# Sonar-Three-Amp-Block.net
KiCad netlist of a schematic drawn in EAGLE
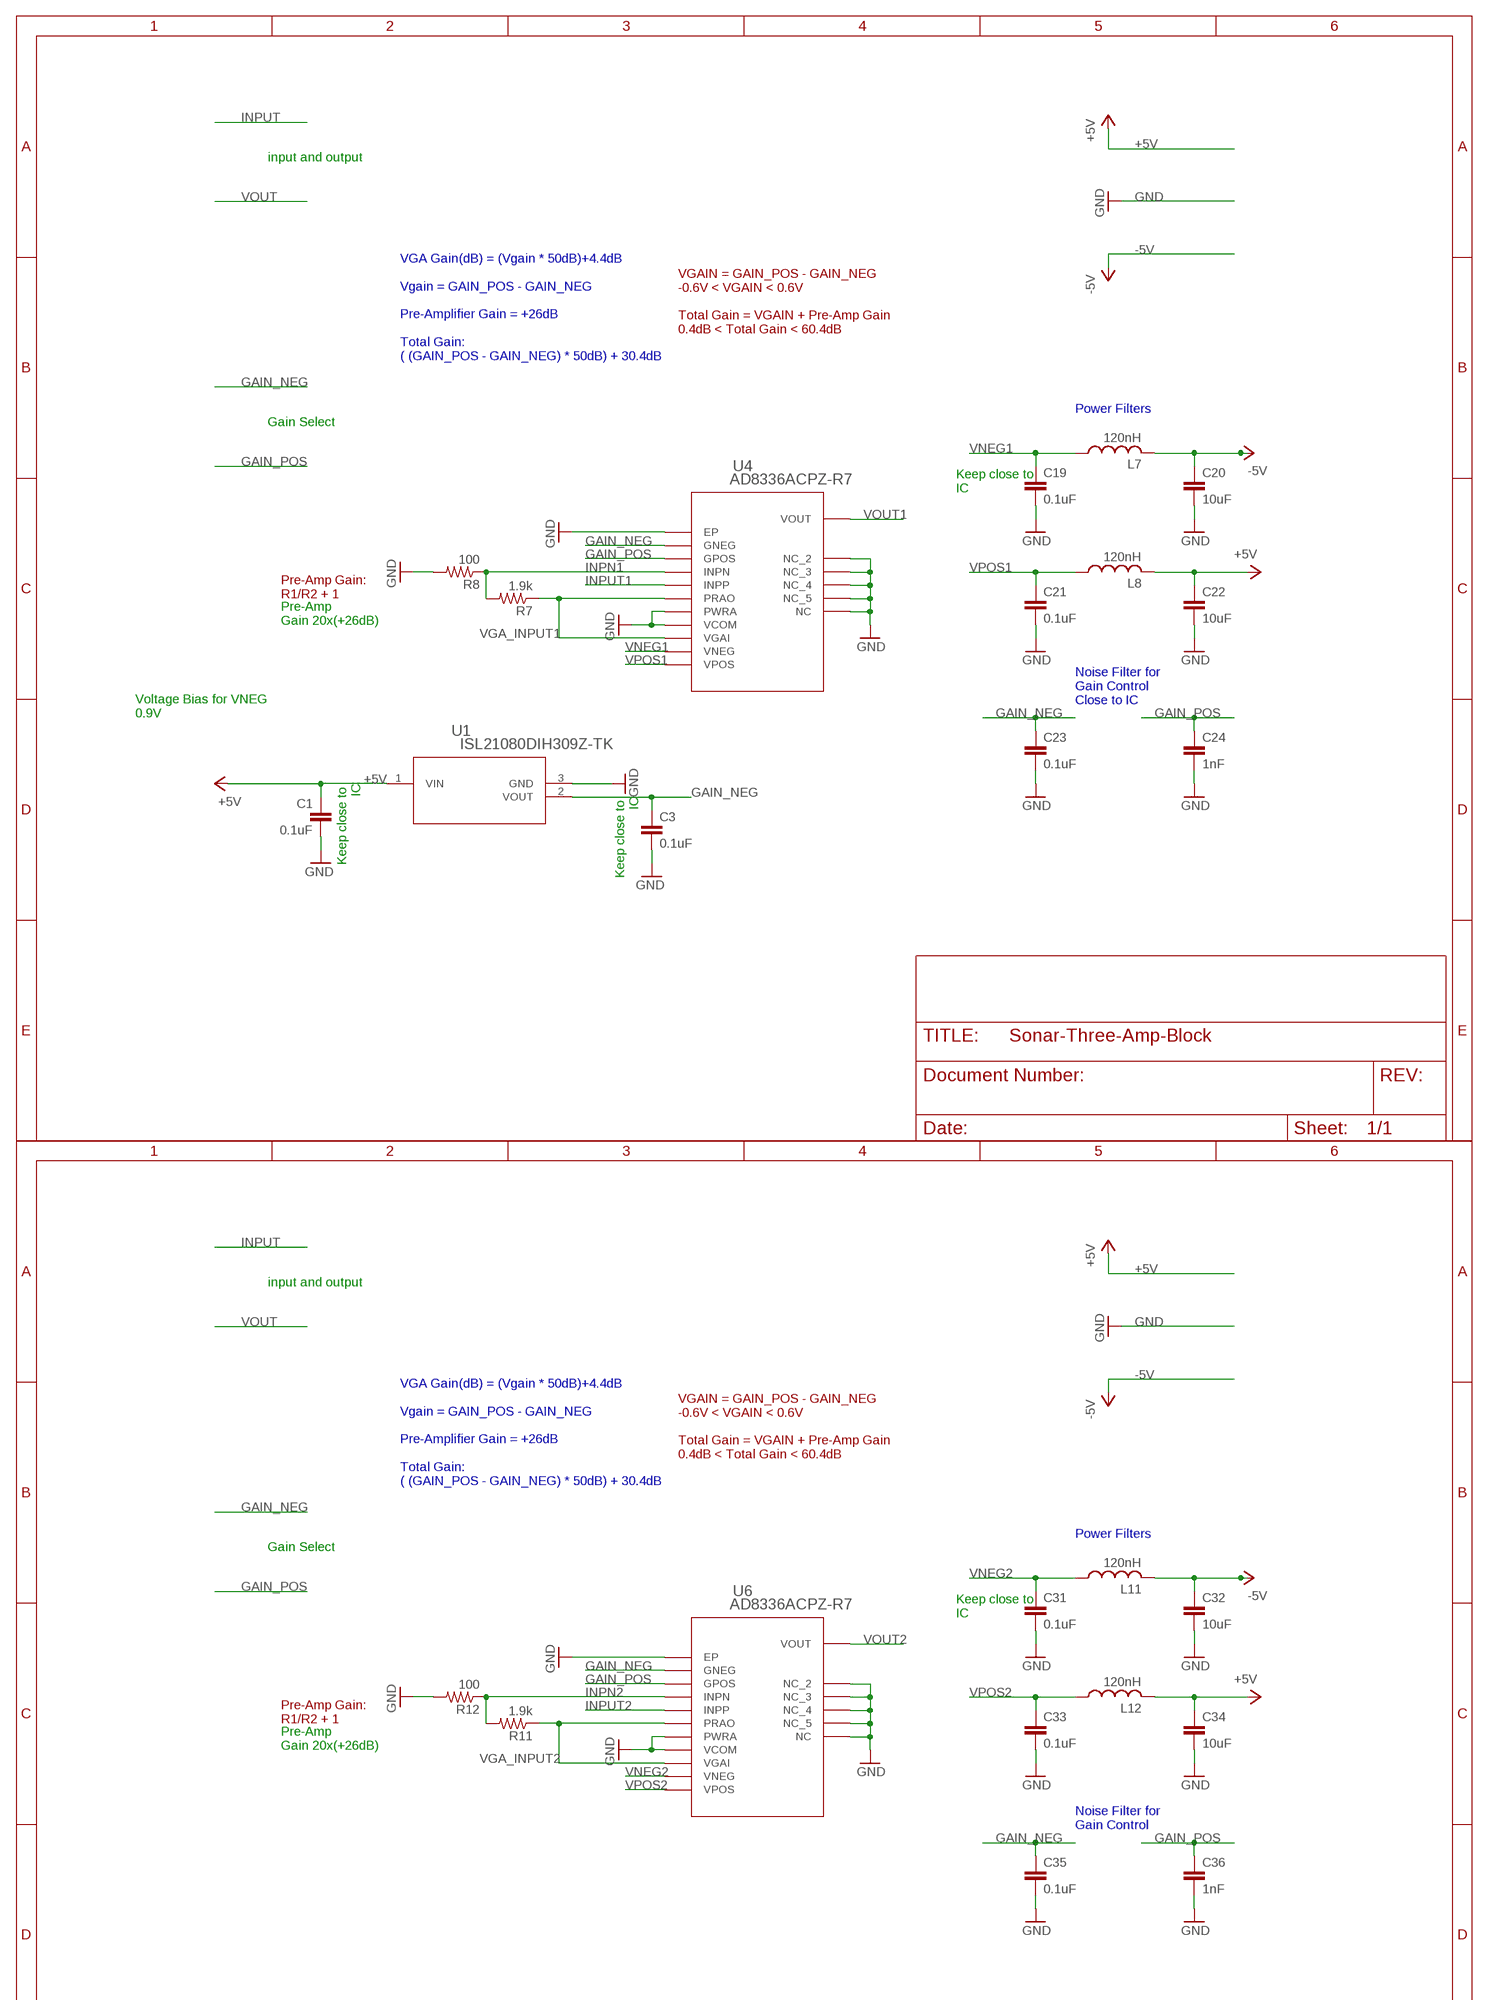
[diagram p0: schematic, sheet 1, part 1 of 2]
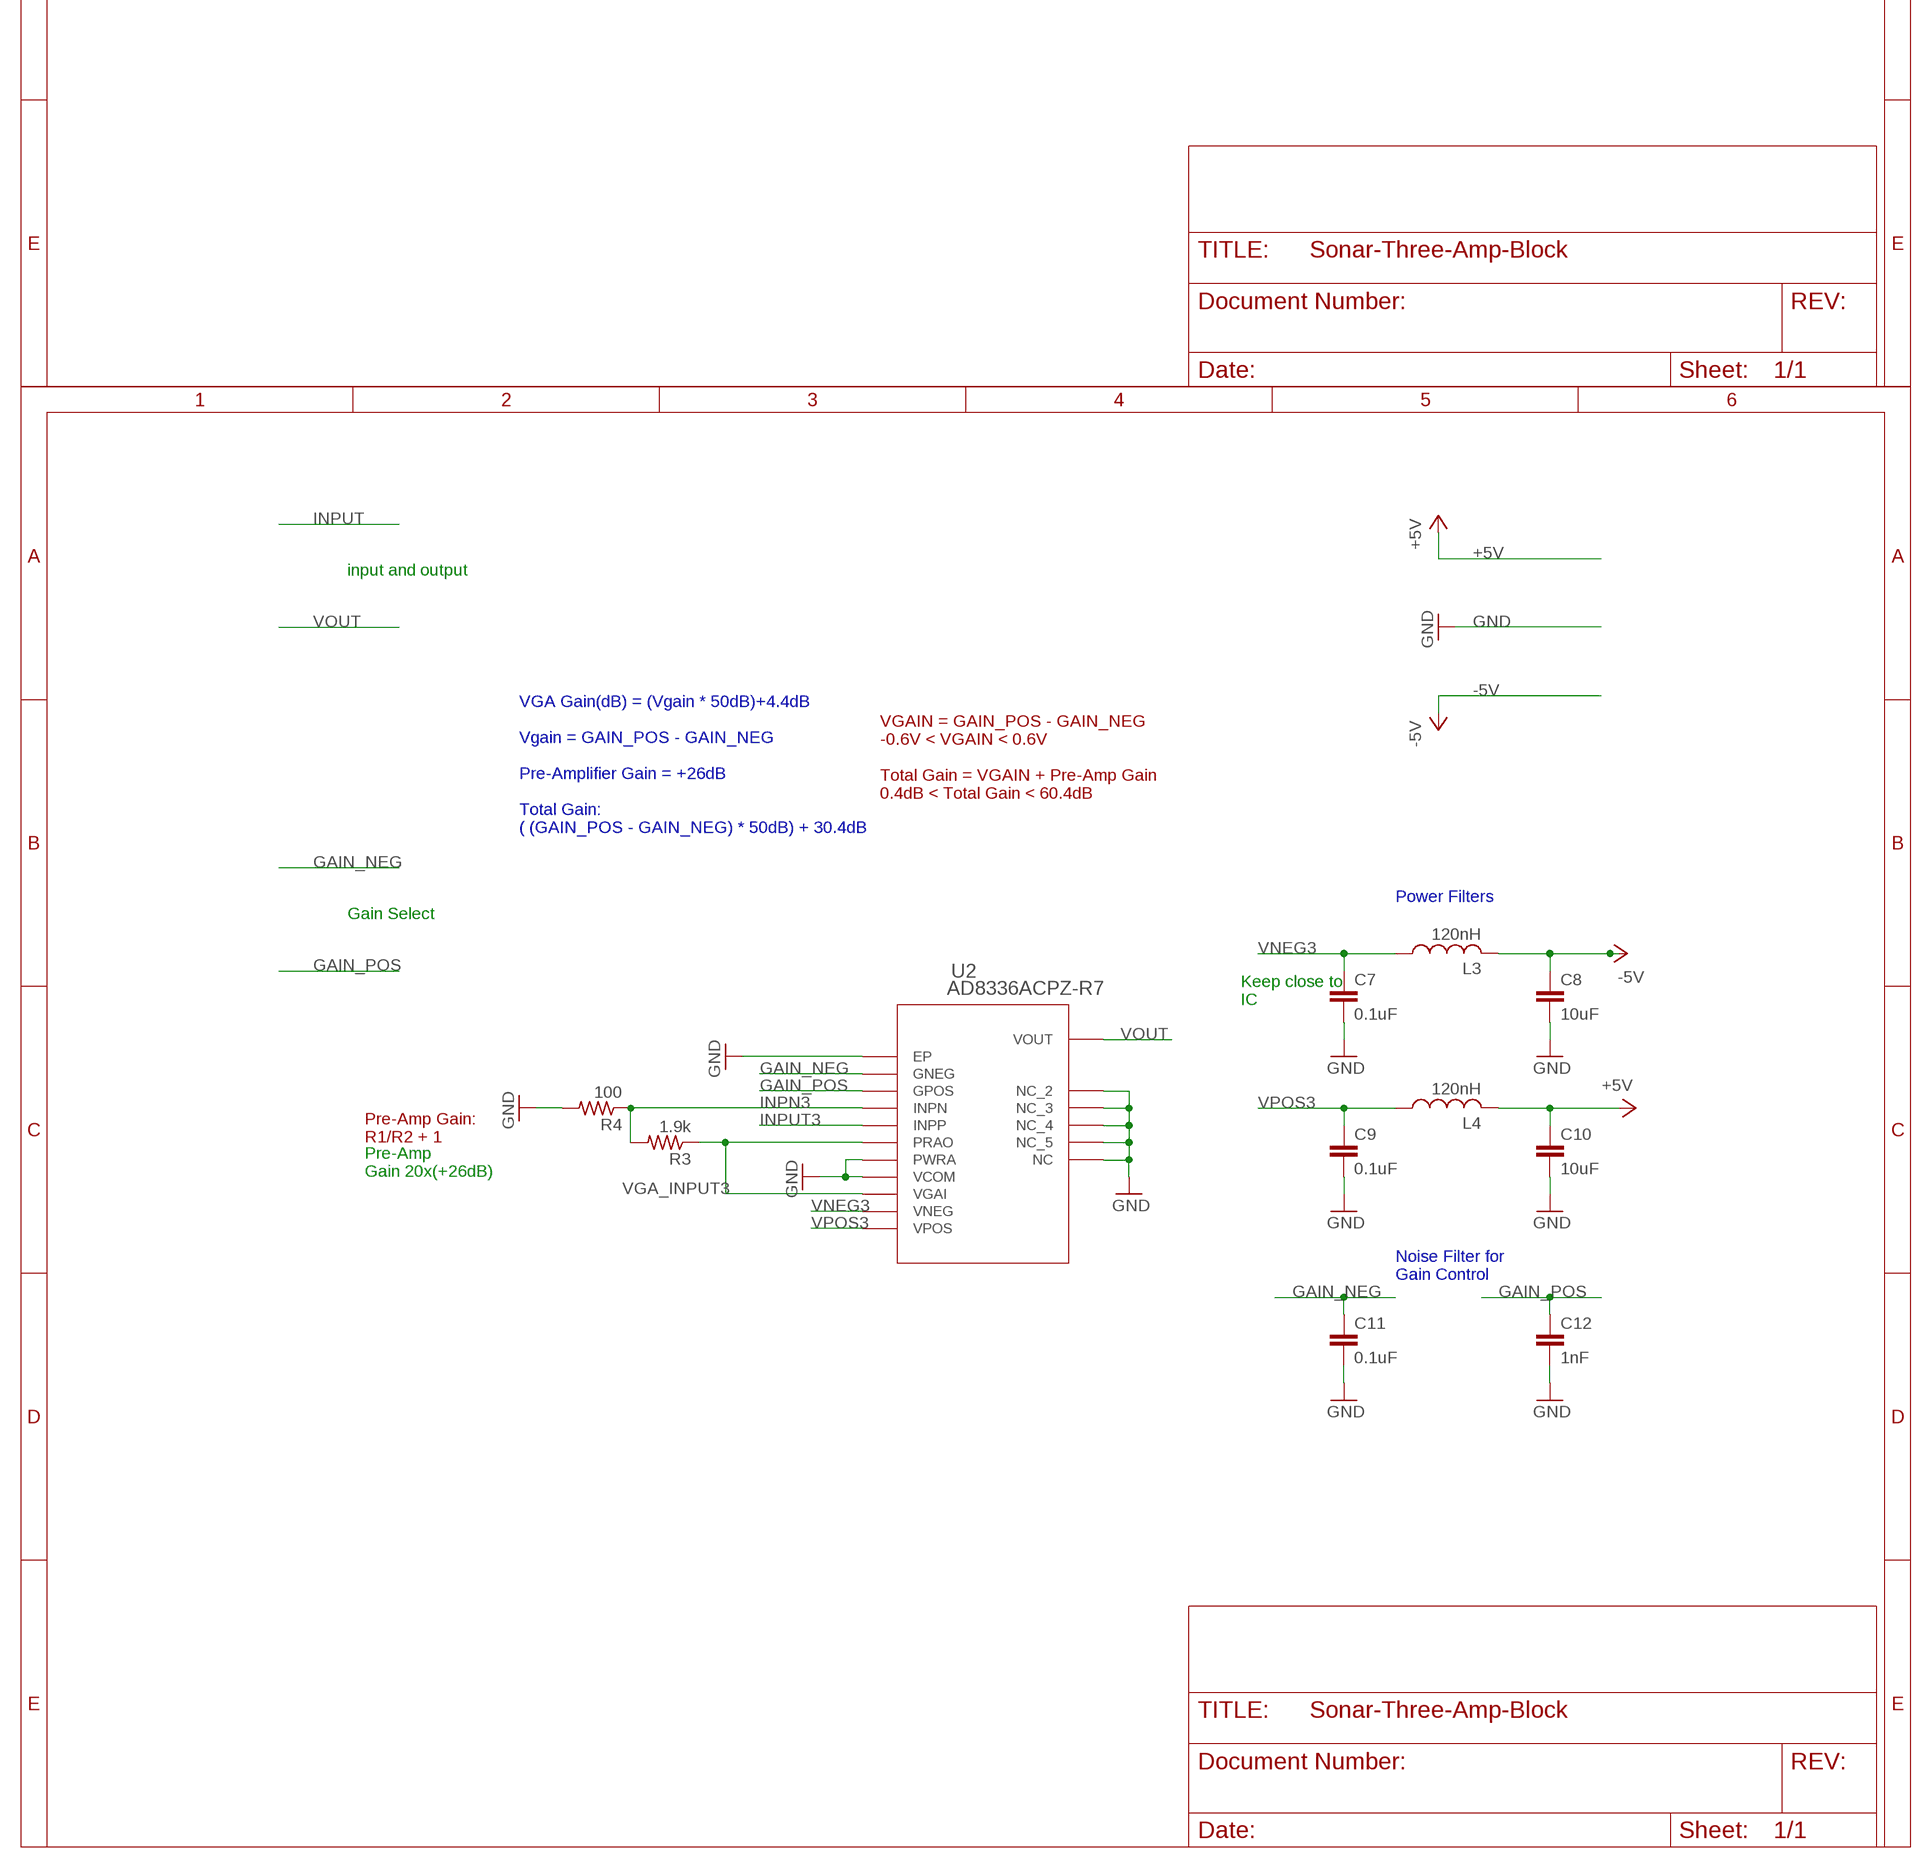
[diagram p1: schematic, sheet 1, part 2 of 2]

(export (version "E")
  (design (tool "Eeschema 10.0.6"))
  (components
    (comp (ref "C1")
      (value "0.1uF")
      (footprint "eagle-import:C0603")
      (libsource (lib "eagle-import") (part "C-EUC0603"))
    )
    (comp (ref "C3")
      (value "0.1uF")
      (footprint "eagle-import:C0603")
      (libsource (lib "eagle-import") (part "C-EUC0603"))
    )
    (comp (ref "C7")
      (value "0.1uF")
      (footprint "eagle-import:C0603")
      (libsource (lib "eagle-import") (part "C-EUC0603"))
    )
    (comp (ref "C8")
      (value "10uF")
      (footprint "eagle-import:C1206")
      (libsource (lib "eagle-import") (part "resistor_348_C-EUC1206"))
    )
    (comp (ref "C9")
      (value "0.1uF")
      (footprint "eagle-import:C0603")
      (libsource (lib "eagle-import") (part "C-EUC0603"))
    )
    (comp (ref "C10")
      (value "10uF")
      (footprint "eagle-import:C1206")
      (libsource (lib "eagle-import") (part "resistor_348_C-EUC1206"))
    )
    (comp (ref "C11")
      (value "0.1uF")
      (footprint "eagle-import:C0603")
      (libsource (lib "eagle-import") (part "C-EUC0603"))
    )
    (comp (ref "C12")
      (value "1nF")
      (footprint "eagle-import:C0603")
      (libsource (lib "eagle-import") (part "C-EUC0603"))
    )
    (comp (ref "C19")
      (value "0.1uF")
      (footprint "eagle-import:C0603")
      (libsource (lib "eagle-import") (part "C-EUC0603"))
    )
    (comp (ref "C20")
      (value "10uF")
      (footprint "eagle-import:C1206")
      (libsource (lib "eagle-import") (part "resistor_348_C-EUC1206"))
    )
    (comp (ref "C21")
      (value "0.1uF")
      (footprint "eagle-import:C0603")
      (libsource (lib "eagle-import") (part "C-EUC0603"))
    )
    (comp (ref "C22")
      (value "10uF")
      (footprint "eagle-import:C1206")
      (libsource (lib "eagle-import") (part "resistor_348_C-EUC1206"))
    )
    (comp (ref "C23")
      (value "0.1uF")
      (footprint "eagle-import:C0603")
      (libsource (lib "eagle-import") (part "C-EUC0603"))
    )
    (comp (ref "C24")
      (value "1nF")
      (footprint "eagle-import:C0603")
      (libsource (lib "eagle-import") (part "C-EUC0603"))
    )
    (comp (ref "C31")
      (value "0.1uF")
      (footprint "eagle-import:C0603")
      (libsource (lib "eagle-import") (part "C-EUC0603"))
    )
    (comp (ref "C32")
      (value "10uF")
      (footprint "eagle-import:C1206")
      (libsource (lib "eagle-import") (part "resistor_348_C-EUC1206"))
    )
    (comp (ref "C33")
      (value "0.1uF")
      (footprint "eagle-import:C0603")
      (libsource (lib "eagle-import") (part "C-EUC0603"))
    )
    (comp (ref "C34")
      (value "10uF")
      (footprint "eagle-import:C1206")
      (libsource (lib "eagle-import") (part "resistor_348_C-EUC1206"))
    )
    (comp (ref "C35")
      (value "0.1uF")
      (footprint "eagle-import:C0603")
      (libsource (lib "eagle-import") (part "C-EUC0603"))
    )
    (comp (ref "C36")
      (value "1nF")
      (footprint "eagle-import:C0603")
      (libsource (lib "eagle-import") (part "C-EUC0603"))
    )
    (comp (ref "L3")
      (value "120nH")
      (footprint "eagle-import:L3225P")
      (libsource (lib "eagle-import") (part "L-USL3225P"))
    )
    (comp (ref "L4")
      (value "120nH")
      (footprint "eagle-import:L3225P")
      (libsource (lib "eagle-import") (part "L-USL3225P"))
    )
    (comp (ref "L7")
      (value "120nH")
      (footprint "eagle-import:L3225P")
      (libsource (lib "eagle-import") (part "L-USL3225P"))
    )
    (comp (ref "L8")
      (value "120nH")
      (footprint "eagle-import:L3225P")
      (libsource (lib "eagle-import") (part "L-USL3225P"))
    )
    (comp (ref "L11")
      (value "120nH")
      (footprint "eagle-import:L3225P")
      (libsource (lib "eagle-import") (part "L-USL3225P"))
    )
    (comp (ref "L12")
      (value "120nH")
      (footprint "eagle-import:L3225P")
      (libsource (lib "eagle-import") (part "L-USL3225P"))
    )
    (comp (ref "R3")
      (value "1.9k")
      (footprint "eagle-import:R0603")
      (libsource (lib "eagle-import") (part "R-US_R0603"))
    )
    (comp (ref "R4")
      (value "100")
      (footprint "eagle-import:R0603")
      (libsource (lib "eagle-import") (part "R-US_R0603"))
    )
    (comp (ref "R7")
      (value "1.9k")
      (footprint "eagle-import:R0603")
      (libsource (lib "eagle-import") (part "R-US_R0603"))
    )
    (comp (ref "R8")
      (value "100")
      (footprint "eagle-import:R0603")
      (libsource (lib "eagle-import") (part "R-US_R0603"))
    )
    (comp (ref "R11")
      (value "1.9k")
      (footprint "eagle-import:R0603")
      (libsource (lib "eagle-import") (part "R-US_R0603"))
    )
    (comp (ref "R12")
      (value "100")
      (footprint "eagle-import:R0603")
      (libsource (lib "eagle-import") (part "R-US_R0603"))
    )
    (comp (ref "U1")
      (value "ISL21080DIH309Z-TK")
      (footprint "eagle-import:P3_064")
      (fields (field (name "MANUFACTURER_PART_NUMBER") "ISL21080DIH309ZTK"))
      (libsource (lib "eagle-import") (part "ISL21080DIH309Z-TK"))
    )
    (comp (ref "U2")
      (value "AD8336ACPZ-R7")
      (footprint "eagle-import:CP_16_4")
      (fields (field (name "MANUFACTURER_PART_NUMBER") "AD8336ACPZR7"))
      (libsource (lib "eagle-import") (part "AD8336ACPZ-R7"))
    )
    (comp (ref "U4")
      (value "AD8336ACPZ-R7")
      (footprint "eagle-import:CP_16_4")
      (fields (field (name "MANUFACTURER_PART_NUMBER") "AD8336ACPZR7"))
      (libsource (lib "eagle-import") (part "AD8336ACPZ-R7"))
    )
    (comp (ref "U6")
      (value "AD8336ACPZ-R7")
      (footprint "eagle-import:CP_16_4")
      (fields (field (name "MANUFACTURER_PART_NUMBER") "AD8336ACPZR7"))
      (libsource (lib "eagle-import") (part "AD8336ACPZ-R7"))
    )
  )
  (nets
    (net (code "1") (name "+5V") (class "Default")
      (node (ref "C1") (pin "1") (pinfunction "1_1") (pintype "passive"))
      (node (ref "C10") (pin "1") (pinfunction "1_1") (pintype "passive"))
      (node (ref "C22") (pin "1") (pinfunction "1_1") (pintype "passive"))
      (node (ref "C34") (pin "1") (pinfunction "1_1") (pintype "passive"))
      (node (ref "L12") (pin "2") (pinfunction "2_2") (pintype "passive"))
      (node (ref "L4") (pin "2") (pinfunction "2_2") (pintype "passive"))
      (node (ref "L8") (pin "2") (pinfunction "2_2") (pintype "passive"))
      (node (ref "U1") (pin "1") (pinfunction "VIN_1") (pintype "input"))
    )
    (net (code "2") (name "-5V") (class "Default")
      (node (ref "C20") (pin "1") (pinfunction "1_1") (pintype "passive"))
      (node (ref "C32") (pin "1") (pinfunction "1_1") (pintype "passive"))
      (node (ref "C8") (pin "1") (pinfunction "1_1") (pintype "passive"))
      (node (ref "L11") (pin "2") (pinfunction "2_2") (pintype "passive"))
      (node (ref "L3") (pin "2") (pinfunction "2_2") (pintype "passive"))
      (node (ref "L7") (pin "2") (pinfunction "2_2") (pintype "passive"))
    )
    (net (code "3") (name "/GAIN_NEG") (class "Default")
      (node (ref "C11") (pin "1") (pinfunction "1_1") (pintype "passive"))
      (node (ref "C23") (pin "1") (pinfunction "1_1") (pintype "passive"))
      (node (ref "C3") (pin "1") (pinfunction "1_1") (pintype "passive"))
      (node (ref "C35") (pin "1") (pinfunction "1_1") (pintype "passive"))
      (node (ref "U1") (pin "2") (pinfunction "VOUT_2") (pintype "output"))
      (node (ref "U2") (pin "GNEG") (pinfunction "GNEG_GNEG") (pintype "passive"))
      (node (ref "U4") (pin "GNEG") (pinfunction "GNEG_GNEG") (pintype "passive"))
      (node (ref "U6") (pin "GNEG") (pinfunction "GNEG_GNEG") (pintype "passive"))
    )
    (net (code "4") (name "/GAIN_POS") (class "Default")
      (node (ref "C12") (pin "1") (pinfunction "1_1") (pintype "passive"))
      (node (ref "C24") (pin "1") (pinfunction "1_1") (pintype "passive"))
      (node (ref "C36") (pin "1") (pinfunction "1_1") (pintype "passive"))
      (node (ref "U2") (pin "GPOS") (pinfunction "GPOS_GPOS") (pintype "passive"))
      (node (ref "U4") (pin "GPOS") (pinfunction "GPOS_GPOS") (pintype "passive"))
      (node (ref "U6") (pin "GPOS") (pinfunction "GPOS_GPOS") (pintype "passive"))
    )
    (net (code "5") (name "/INPN1") (class "Default")
      (node (ref "R7") (pin "2") (pinfunction "2_2") (pintype "passive"))
      (node (ref "R8") (pin "1") (pinfunction "1_1") (pintype "passive"))
      (node (ref "U4") (pin "INPN") (pinfunction "INPN_INPN") (pintype "passive"))
    )
    (net (code "6") (name "/INPN2") (class "Default")
      (node (ref "R11") (pin "2") (pinfunction "2_2") (pintype "passive"))
      (node (ref "R12") (pin "1") (pinfunction "1_1") (pintype "passive"))
      (node (ref "U6") (pin "INPN") (pinfunction "INPN_INPN") (pintype "passive"))
    )
    (net (code "7") (name "/INPN3") (class "Default")
      (node (ref "R3") (pin "2") (pinfunction "2_2") (pintype "passive"))
      (node (ref "R4") (pin "1") (pinfunction "1_1") (pintype "passive"))
      (node (ref "U2") (pin "INPN") (pinfunction "INPN_INPN") (pintype "passive"))
    )
    (net (code "9") (name "/INPUT1") (class "Default")
      (node (ref "U4") (pin "INPP") (pinfunction "INPP_INPP") (pintype "passive"))
    )
    (net (code "10") (name "/INPUT2") (class "Default")
      (node (ref "U6") (pin "INPP") (pinfunction "INPP_INPP") (pintype "passive"))
    )
    (net (code "11") (name "/INPUT3") (class "Default")
      (node (ref "U2") (pin "INPP") (pinfunction "INPP_INPP") (pintype "passive"))
    )
    (net (code "12") (name "/VGA_INPUT1") (class "Default")
      (node (ref "R7") (pin "1") (pinfunction "1_1") (pintype "passive"))
      (node (ref "U4") (pin "PRAO") (pinfunction "PRAO_PRAO") (pintype "passive"))
      (node (ref "U4") (pin "VGAI") (pinfunction "VGAI_VGAI") (pintype "passive"))
    )
    (net (code "13") (name "/VGA_INPUT2") (class "Default")
      (node (ref "R11") (pin "1") (pinfunction "1_1") (pintype "passive"))
      (node (ref "U6") (pin "PRAO") (pinfunction "PRAO_PRAO") (pintype "passive"))
      (node (ref "U6") (pin "VGAI") (pinfunction "VGAI_VGAI") (pintype "passive"))
    )
    (net (code "14") (name "/VGA_INPUT3") (class "Default")
      (node (ref "R3") (pin "1") (pinfunction "1_1") (pintype "passive"))
      (node (ref "U2") (pin "PRAO") (pinfunction "PRAO_PRAO") (pintype "passive"))
      (node (ref "U2") (pin "VGAI") (pinfunction "VGAI_VGAI") (pintype "passive"))
    )
    (net (code "15") (name "/VNEG1") (class "Default")
      (node (ref "C19") (pin "1") (pinfunction "1_1") (pintype "passive"))
      (node (ref "L7") (pin "1") (pinfunction "1_1") (pintype "passive"))
      (node (ref "U4") (pin "VNEG") (pinfunction "VNEG_VNEG") (pintype "passive"))
    )
    (net (code "16") (name "/VNEG2") (class "Default")
      (node (ref "C31") (pin "1") (pinfunction "1_1") (pintype "passive"))
      (node (ref "L11") (pin "1") (pinfunction "1_1") (pintype "passive"))
      (node (ref "U6") (pin "VNEG") (pinfunction "VNEG_VNEG") (pintype "passive"))
    )
    (net (code "17") (name "/VNEG3") (class "Default")
      (node (ref "C7") (pin "1") (pinfunction "1_1") (pintype "passive"))
      (node (ref "L3") (pin "1") (pinfunction "1_1") (pintype "passive"))
      (node (ref "U2") (pin "VNEG") (pinfunction "VNEG_VNEG") (pintype "passive"))
    )
    (net (code "18") (name "/VOUT") (class "Default")
      (node (ref "U2") (pin "VOUT") (pinfunction "VOUT_VOUT") (pintype "passive"))
    )
    (net (code "19") (name "/VOUT1") (class "Default")
      (node (ref "U4") (pin "VOUT") (pinfunction "VOUT_VOUT") (pintype "passive"))
    )
    (net (code "20") (name "/VOUT2") (class "Default")
      (node (ref "U6") (pin "VOUT") (pinfunction "VOUT_VOUT") (pintype "passive"))
    )
    (net (code "21") (name "/VPOS1") (class "Default")
      (node (ref "C21") (pin "1") (pinfunction "1_1") (pintype "passive"))
      (node (ref "L8") (pin "1") (pinfunction "1_1") (pintype "passive"))
      (node (ref "U4") (pin "VPOS") (pinfunction "VPOS_VPOS") (pintype "passive"))
    )
    (net (code "22") (name "/VPOS2") (class "Default")
      (node (ref "C33") (pin "1") (pinfunction "1_1") (pintype "passive"))
      (node (ref "L12") (pin "1") (pinfunction "1_1") (pintype "passive"))
      (node (ref "U6") (pin "VPOS") (pinfunction "VPOS_VPOS") (pintype "passive"))
    )
    (net (code "23") (name "/VPOS3") (class "Default")
      (node (ref "C9") (pin "1") (pinfunction "1_1") (pintype "passive"))
      (node (ref "L4") (pin "1") (pinfunction "1_1") (pintype "passive"))
      (node (ref "U2") (pin "VPOS") (pinfunction "VPOS_VPOS") (pintype "passive"))
    )
    (net (code "24") (name "GND") (class "Default")
      (node (ref "C1") (pin "2") (pinfunction "2_2") (pintype "passive"))
      (node (ref "C10") (pin "2") (pinfunction "2_2") (pintype "passive"))
      (node (ref "C11") (pin "2") (pinfunction "2_2") (pintype "passive"))
      (node (ref "C12") (pin "2") (pinfunction "2_2") (pintype "passive"))
      (node (ref "C19") (pin "2") (pinfunction "2_2") (pintype "passive"))
      (node (ref "C20") (pin "2") (pinfunction "2_2") (pintype "passive"))
      (node (ref "C21") (pin "2") (pinfunction "2_2") (pintype "passive"))
      (node (ref "C22") (pin "2") (pinfunction "2_2") (pintype "passive"))
      (node (ref "C23") (pin "2") (pinfunction "2_2") (pintype "passive"))
      (node (ref "C24") (pin "2") (pinfunction "2_2") (pintype "passive"))
      (node (ref "C3") (pin "2") (pinfunction "2_2") (pintype "passive"))
      (node (ref "C31") (pin "2") (pinfunction "2_2") (pintype "passive"))
      (node (ref "C32") (pin "2") (pinfunction "2_2") (pintype "passive"))
      (node (ref "C33") (pin "2") (pinfunction "2_2") (pintype "passive"))
      (node (ref "C34") (pin "2") (pinfunction "2_2") (pintype "passive"))
      (node (ref "C35") (pin "2") (pinfunction "2_2") (pintype "passive"))
      (node (ref "C36") (pin "2") (pinfunction "2_2") (pintype "passive"))
      (node (ref "C7") (pin "2") (pinfunction "2_2") (pintype "passive"))
      (node (ref "C8") (pin "2") (pinfunction "2_2") (pintype "passive"))
      (node (ref "C9") (pin "2") (pinfunction "2_2") (pintype "passive"))
      (node (ref "R12") (pin "2") (pinfunction "2_2") (pintype "passive"))
      (node (ref "R4") (pin "2") (pinfunction "2_2") (pintype "passive"))
      (node (ref "R8") (pin "2") (pinfunction "2_2") (pintype "passive"))
      (node (ref "U1") (pin "3") (pinfunction "GND_3") (pintype "power_in"))
      (node (ref "U2") (pin "GND1") (pinfunction "EP_GND1") (pintype "passive"))
      (node (ref "U2") (pin "NC") (pinfunction "NC_NC") (pintype "passive"))
      (node (ref "U2") (pin "NC1") (pinfunction "NC_2_NC1") (pintype "passive"))
      (node (ref "U2") (pin "NC2") (pinfunction "NC_3_NC2") (pintype "passive"))
      (node (ref "U2") (pin "NC3") (pinfunction "NC_4_NC3") (pintype "passive"))
      (node (ref "U2") (pin "NC4") (pinfunction "NC_5_NC4") (pintype "passive"))
      (node (ref "U2") (pin "PWRA") (pinfunction "PWRA_PWRA") (pintype "passive"))
      (node (ref "U2") (pin "VCOM") (pinfunction "VCOM_VCOM") (pintype "passive"))
      (node (ref "U4") (pin "GND1") (pinfunction "EP_GND1") (pintype "passive"))
      (node (ref "U4") (pin "NC") (pinfunction "NC_NC") (pintype "passive"))
      (node (ref "U4") (pin "NC1") (pinfunction "NC_2_NC1") (pintype "passive"))
      (node (ref "U4") (pin "NC2") (pinfunction "NC_3_NC2") (pintype "passive"))
      (node (ref "U4") (pin "NC3") (pinfunction "NC_4_NC3") (pintype "passive"))
      (node (ref "U4") (pin "NC4") (pinfunction "NC_5_NC4") (pintype "passive"))
      (node (ref "U4") (pin "PWRA") (pinfunction "PWRA_PWRA") (pintype "passive"))
      (node (ref "U4") (pin "VCOM") (pinfunction "VCOM_VCOM") (pintype "passive"))
      (node (ref "U6") (pin "GND1") (pinfunction "EP_GND1") (pintype "passive"))
      (node (ref "U6") (pin "NC") (pinfunction "NC_NC") (pintype "passive"))
      (node (ref "U6") (pin "NC1") (pinfunction "NC_2_NC1") (pintype "passive"))
      (node (ref "U6") (pin "NC2") (pinfunction "NC_3_NC2") (pintype "passive"))
      (node (ref "U6") (pin "NC3") (pinfunction "NC_4_NC3") (pintype "passive"))
      (node (ref "U6") (pin "NC4") (pinfunction "NC_5_NC4") (pintype "passive"))
      (node (ref "U6") (pin "PWRA") (pinfunction "PWRA_PWRA") (pintype "passive"))
      (node (ref "U6") (pin "VCOM") (pinfunction "VCOM_VCOM") (pintype "passive"))
    )
  )
)
